# lipo-charger-SMD.net
KiCad netlist of a schematic drawn in EAGLE
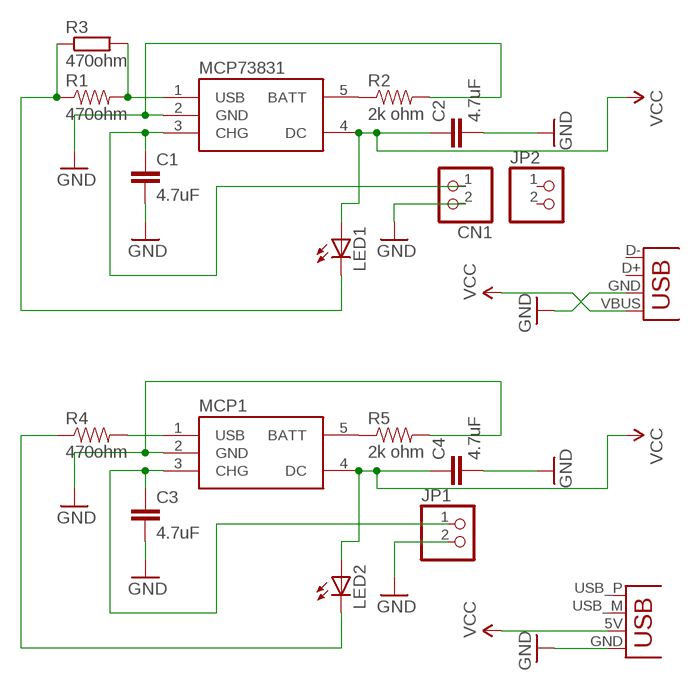
[diagram p0: schematic, sheet 1]

(export (version "E")
  (design (tool "Eeschema 10.0.6"))
  (components
    (comp (ref "C1")
      (value "4.7uF")
      (footprint "eagle-import:0805")
      (libsource (lib "eagle-import") (part "CAP0805"))
    )
    (comp (ref "C2")
      (value "4.7uF")
      (footprint "eagle-import:0805")
      (libsource (lib "eagle-import") (part "CAP0805"))
    )
    (comp (ref "C3")
      (value "4.7uF")
      (footprint "eagle-import:0805")
      (libsource (lib "eagle-import") (part "CAP0805"))
    )
    (comp (ref "C4")
      (value "4.7uF")
      (footprint "eagle-import:0805")
      (libsource (lib "eagle-import") (part "CAP0805"))
    )
    (comp (ref "CN1")
      (value "JST_2PIN-THM")
      (footprint "eagle-import:JST-PH-2-THM")
      (libsource (lib "eagle-import") (part "JST_2PIN-THM"))
    )
    (comp (ref "JP1")
      (value "PINHD-1X2/90")
      (footprint "eagle-import:1X02_90")
      (libsource (lib "eagle-import") (part "PINHD-1X2/90"))
    )
    (comp (ref "JP2")
      (value "PINHD-1X2/90")
      (footprint "eagle-import:1X02_90")
      (libsource (lib "eagle-import") (part "PINHD-1X2/90"))
    )
    (comp (ref "LED1")
      (value "LEDCHIP-LED0805")
      (footprint "eagle-import:CHIP-LED0805")
      (libsource (lib "eagle-import") (part "LEDCHIP-LED0805"))
    )
    (comp (ref "LED2")
      (value "LEDCHIP-LED0805")
      (footprint "eagle-import:CHIP-LED0805")
      (libsource (lib "eagle-import") (part "LEDCHIP-LED0805"))
    )
    (comp (ref "MCP1")
      (value "MAX1555")
      (footprint "eagle-import:SOT23-5")
      (libsource (lib "eagle-import") (part "MAX1555"))
    )
    (comp (ref "MCP73831")
      (value "MAX1555")
      (footprint "eagle-import:SOT23-5")
      (libsource (lib "eagle-import") (part "MAX1555"))
    )
    (comp (ref "R1")
      (value "470ohm")
      (footprint "eagle-import:0805")
      (libsource (lib "eagle-import") (part "RESISTOR"))
    )
    (comp (ref "R2")
      (value "2k ohm")
      (footprint "eagle-import:0805")
      (libsource (lib "eagle-import") (part "RESISTOR"))
    )
    (comp (ref "R3")
      (value "470ohm")
      (footprint "eagle-import:0309V")
      (libsource (lib "eagle-import") (part "R-EU_0309/V"))
    )
    (comp (ref "R4")
      (value "470ohm")
      (footprint "eagle-import:0805")
      (libsource (lib "eagle-import") (part "RESISTOR"))
    )
    (comp (ref "R5")
      (value "2k ohm")
      (footprint "eagle-import:0805")
      (libsource (lib "eagle-import") (part "RESISTOR"))
    )
    (comp (ref "X2")
      (value "USB-A-H")
      (footprint "eagle-import:USB-A-H")
      (libsource (lib "eagle-import") (part "USB-A-H"))
    )
    (comp (ref "X3")
      (value "USBPCB")
      (footprint "eagle-import:USB-A-PCB")
      (libsource (lib "eagle-import") (part "USBPCB"))
    )
  )
  (nets
    (net (code "1") (name "GND") (class "Default")
      (node (ref "C1") (pin "2") (pinfunction "2_2") (pintype "passive"))
      (node (ref "C2") (pin "2") (pinfunction "2_2") (pintype "passive"))
      (node (ref "C3") (pin "2") (pinfunction "2_2") (pintype "passive"))
      (node (ref "C4") (pin "2") (pinfunction "2_2") (pintype "passive"))
      (node (ref "CN1") (pin "2") (pinfunction "1_2") (pintype "passive"))
      (node (ref "JP1") (pin "2") (pinfunction "2_2") (pintype "passive"))
      (node (ref "MCP1") (pin "2") (pinfunction "GND_2") (pintype "bidirectional"))
      (node (ref "MCP73831") (pin "2") (pinfunction "GND_2") (pintype "bidirectional"))
      (node (ref "R2") (pin "2") (pinfunction "2_2") (pintype "passive"))
      (node (ref "R5") (pin "2") (pinfunction "2_2") (pintype "passive"))
      (node (ref "X2") (pin "GND") (pinfunction "VBUS_GND") (pintype "bidirectional"))
      (node (ref "X3") (pin "GND") (pinfunction "GND_GND") (pintype "bidirectional"))
    )
    (net (code "2") (name "Net-(CN1-2)") (class "Default")
      (node (ref "C1") (pin "1") (pinfunction "1_1") (pintype "passive"))
      (node (ref "CN1") (pin "1") (pinfunction "2_1") (pintype "passive"))
      (node (ref "MCP73831") (pin "3") (pinfunction "CHG_3") (pintype "bidirectional"))
    )
    (net (code "3") (name "Net-(LED1-PadC)") (class "Default")
      (node (ref "LED1") (pin "C") (pinfunction "C_C") (pintype "passive"))
      (node (ref "R1") (pin "1") (pinfunction "1_1") (pintype "passive"))
      (node (ref "R3") (pin "1") (pinfunction "1_1") (pintype "passive"))
    )
    (net (code "4") (name "Net-(LED2-PadC)") (class "Default")
      (node (ref "LED2") (pin "C") (pinfunction "C_C") (pintype "passive"))
      (node (ref "R4") (pin "1") (pinfunction "1_1") (pintype "passive"))
    )
    (net (code "5") (name "Net-(MCP1-BATT)") (class "Default")
      (node (ref "MCP1") (pin "5") (pinfunction "BATT_5") (pintype "bidirectional"))
      (node (ref "R5") (pin "1") (pinfunction "1_1") (pintype "passive"))
    )
    (net (code "6") (name "Net-(MCP1-CHG)") (class "Default")
      (node (ref "C3") (pin "1") (pinfunction "1_1") (pintype "passive"))
      (node (ref "JP1") (pin "1") (pinfunction "1_1") (pintype "passive"))
      (node (ref "MCP1") (pin "3") (pinfunction "CHG_3") (pintype "bidirectional"))
    )
    (net (code "7") (name "Net-(MCP1-USB)") (class "Default")
      (node (ref "MCP1") (pin "1") (pinfunction "USB_1") (pintype "bidirectional"))
      (node (ref "R4") (pin "2") (pinfunction "2_2") (pintype "passive"))
    )
    (net (code "8") (name "Net-(MCP73831-BATT)") (class "Default")
      (node (ref "MCP73831") (pin "5") (pinfunction "BATT_5") (pintype "bidirectional"))
      (node (ref "R2") (pin "1") (pinfunction "1_1") (pintype "passive"))
    )
    (net (code "9") (name "Net-(MCP73831-USB)") (class "Default")
      (node (ref "MCP73831") (pin "1") (pinfunction "USB_1") (pintype "bidirectional"))
      (node (ref "R1") (pin "2") (pinfunction "2_2") (pintype "passive"))
      (node (ref "R3") (pin "2") (pinfunction "2_2") (pintype "passive"))
    )
    (net (code "10") (name "VCC") (class "Default")
      (node (ref "C2") (pin "1") (pinfunction "1_1") (pintype "passive"))
      (node (ref "C4") (pin "1") (pinfunction "1_1") (pintype "passive"))
      (node (ref "LED1") (pin "A") (pinfunction "A_A") (pintype "passive"))
      (node (ref "LED2") (pin "A") (pinfunction "A_A") (pintype "passive"))
      (node (ref "MCP1") (pin "4") (pinfunction "DC_4") (pintype "bidirectional"))
      (node (ref "MCP73831") (pin "4") (pinfunction "DC_4") (pintype "bidirectional"))
      (node (ref "X2") (pin "VBUS") (pinfunction "GND_VBUS") (pintype "bidirectional"))
      (node (ref "X3") (pin "5V") (pinfunction "VBUS_5V") (pintype "bidirectional"))
    )
    (net (code "11") (name "unconnected-(JP2-Pad1)") (class "Default")
      (node (ref "JP2") (pin "1") (pinfunction "1_1") (pintype "passive"))
    )
    (net (code "12") (name "unconnected-(JP2-Pad2)") (class "Default")
      (node (ref "JP2") (pin "2") (pinfunction "2_2") (pintype "passive"))
    )
    (net (code "13") (name "unconnected-(X2-D+-PadD-)") (class "Default")
      (node (ref "X2") (pin "D-") (pinfunction "D+_D-") (pintype "bidirectional"))
    )
    (net (code "14") (name "unconnected-(X2-D--PadD+)") (class "Default")
      (node (ref "X2") (pin "D+") (pinfunction "D-_D+") (pintype "bidirectional"))
    )
    (net (code "15") (name "unconnected-(X3-D+-PadUSB_P)") (class "Default")
      (node (ref "X3") (pin "USB_P") (pinfunction "D+_USB_P") (pintype "bidirectional"))
    )
    (net (code "16") (name "unconnected-(X3-D--PadUSB_M)") (class "Default")
      (node (ref "X3") (pin "USB_M") (pinfunction "D-_USB_M") (pintype "bidirectional"))
    )
  )
)
